# 08_SD_card.net
KiCad netlist of a schematic drawn in Altium Designer
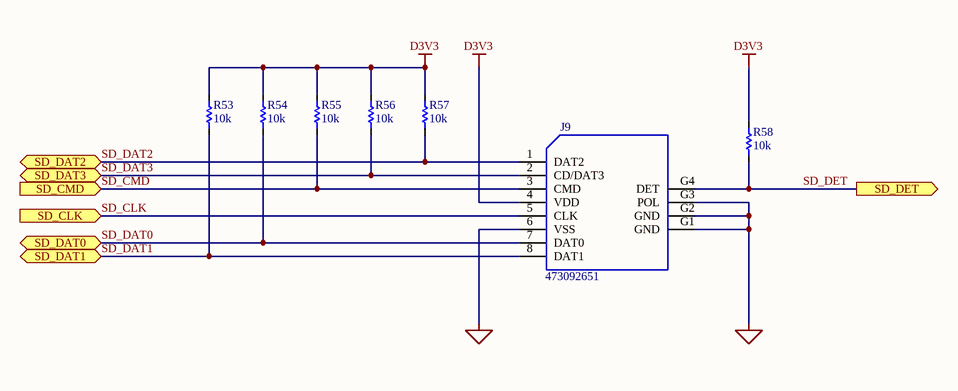
[diagram p0: 08_SD_card.SchDoc]

(export (version "E")
  (design (tool "Eeschema 10.0.6"))
  (components
    (comp (ref "J9")
      (value "473092651")
      (footprint "473092651")
      (description "micro SD card header, detect pin, SMD")
      (libsource (lib "AD15_libpkg") (part "473092651"))
    )
    (comp (ref "R53")
      (value "10k")
      (footprint "R0402")
      (description "RES,10k,1%,1/16W,0402")
      (libsource (lib "R0402") (part "RES012"))
    )
    (comp (ref "R54")
      (value "10k")
      (footprint "R0402")
      (description "RES,10k,1%,1/16W,0402")
      (libsource (lib "R0402") (part "RES012"))
    )
    (comp (ref "R55")
      (value "10k")
      (footprint "R0402")
      (description "RES,10k,1%,1/16W,0402")
      (libsource (lib "R0402") (part "RES012"))
    )
    (comp (ref "R56")
      (value "10k")
      (footprint "R0402")
      (description "RES,10k,1%,1/16W,0402")
      (libsource (lib "R0402") (part "RES012"))
    )
    (comp (ref "R57")
      (value "10k")
      (footprint "R0402")
      (description "RES,10k,1%,1/16W,0402")
      (libsource (lib "R0402") (part "RES012"))
    )
    (comp (ref "R58")
      (value "10k")
      (footprint "R0402")
      (description "RES,10k,1%,1/16W,0402")
      (libsource (lib "R0402") (part "RES012"))
    )
  )
  (nets
    (net (code "1") (name "/SD_CLK") (class "Default")
      (node (ref "J9") (pin "5") (pinfunction "CLK_5") (pintype "passive"))
    )
    (net (code "2") (name "/SD_CMD") (class "Default")
      (node (ref "J9") (pin "3") (pinfunction "CMD_3") (pintype "passive"))
      (node (ref "R55") (pin "1") (pinfunction "0_1") (pintype "passive"))
    )
    (net (code "3") (name "/SD_DAT0") (class "Default")
      (node (ref "J9") (pin "7") (pinfunction "DAT0_7") (pintype "passive"))
      (node (ref "R54") (pin "1") (pinfunction "0_1") (pintype "passive"))
    )
    (net (code "4") (name "/SD_DAT1") (class "Default")
      (node (ref "J9") (pin "8") (pinfunction "DAT1_8") (pintype "passive"))
      (node (ref "R53") (pin "1") (pinfunction "0_1") (pintype "passive"))
    )
    (net (code "5") (name "/SD_DAT2") (class "Default")
      (node (ref "J9") (pin "1") (pinfunction "DAT2_1") (pintype "passive"))
      (node (ref "R57") (pin "1") (pinfunction "0_1") (pintype "passive"))
    )
    (net (code "6") (name "/SD_DAT3") (class "Default")
      (node (ref "J9") (pin "2") (pinfunction "CD/DAT3_2") (pintype "passive"))
      (node (ref "R56") (pin "1") (pinfunction "0_1") (pintype "passive"))
    )
    (net (code "7") (name "/SD_DET") (class "Default")
      (node (ref "J9") (pin "G4") (pinfunction "DET_G4") (pintype "passive"))
      (node (ref "R58") (pin "1") (pinfunction "0_1") (pintype "passive"))
    )
    (net (code "8") (name "D3V3") (class "Default")
      (node (ref "J9") (pin "4") (pinfunction "VDD_4") (pintype "passive"))
      (node (ref "R53") (pin "2") (pinfunction "2_2") (pintype "passive"))
      (node (ref "R54") (pin "2") (pinfunction "2_2") (pintype "passive"))
      (node (ref "R55") (pin "2") (pinfunction "2_2") (pintype "passive"))
      (node (ref "R56") (pin "2") (pinfunction "2_2") (pintype "passive"))
      (node (ref "R57") (pin "2") (pinfunction "2_2") (pintype "passive"))
      (node (ref "R58") (pin "2") (pinfunction "2_2") (pintype "passive"))
    )
    (net (code "9") (name "GND") (class "Default")
      (node (ref "J9") (pin "6") (pinfunction "VSS_6") (pintype "passive"))
      (node (ref "J9") (pin "G1") (pinfunction "GND_G1") (pintype "passive"))
      (node (ref "J9") (pin "G2") (pinfunction "GND_G2") (pintype "passive"))
      (node (ref "J9") (pin "G3") (pinfunction "POL_G3") (pintype "passive"))
    )
  )
)
